# receiver.net
KiCad netlist of a schematic drawn in EAGLE
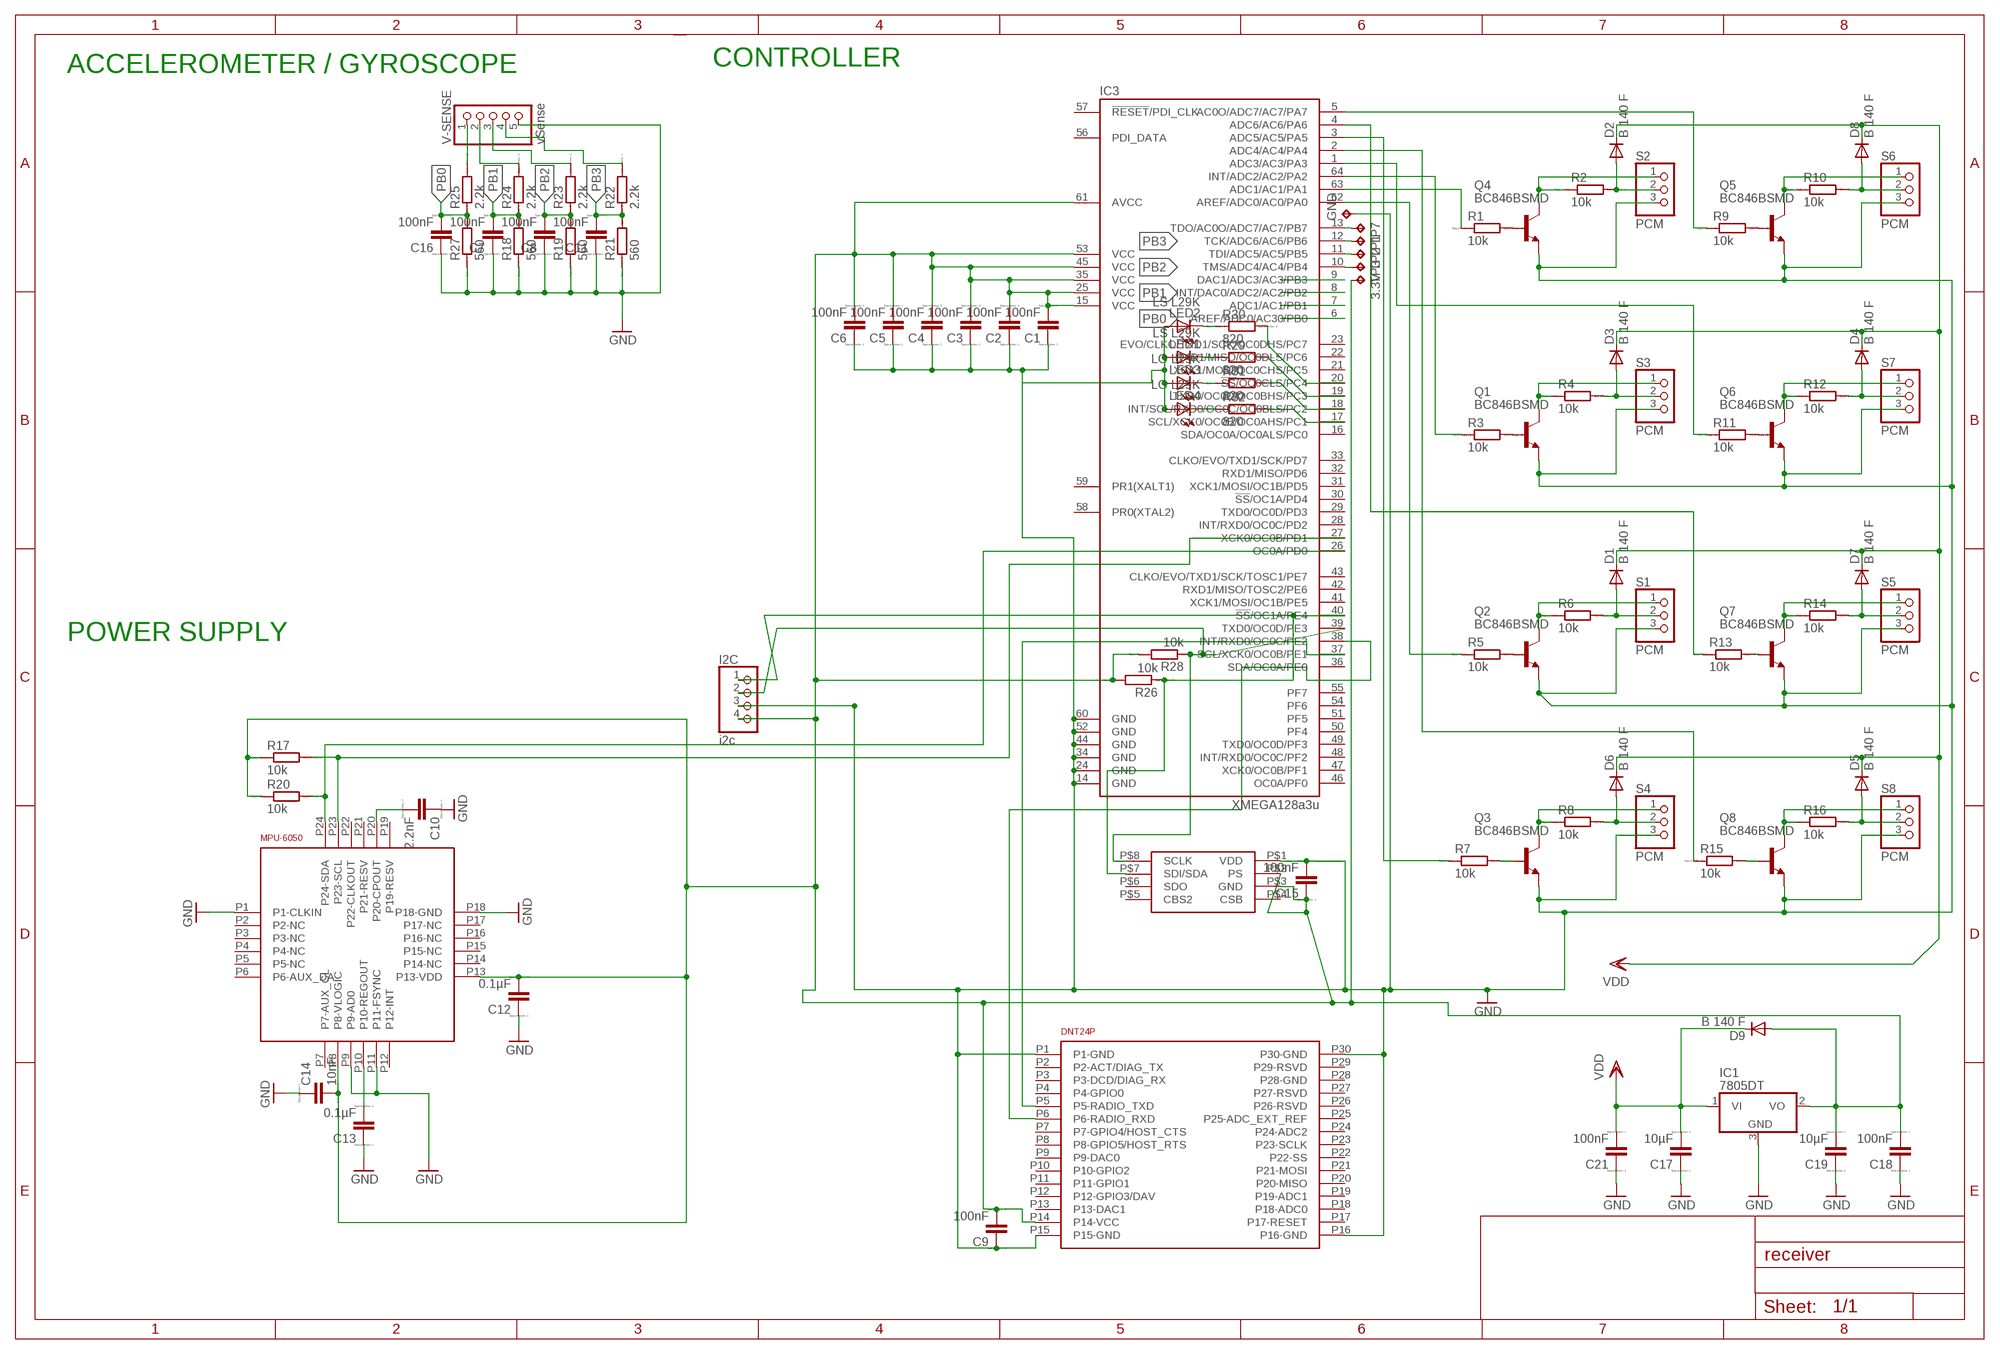
[diagram p0: schematic, sheet 1]

(export (version "E")
  (design (tool "Eeschema 10.0.6"))
  (components
    (comp (ref "3.3V")
      (value "TPTP08R")
      (footprint "eagle-import:TP08R")
      (libsource (lib "eagle-import") (part "TPTP08R"))
    )
    (comp (ref "C1")
      (value "100nF")
      (footprint "eagle-import:C0603")
      (libsource (lib "eagle-import") (part "CC0603"))
    )
    (comp (ref "C2")
      (value "100nF")
      (footprint "eagle-import:C0603")
      (libsource (lib "eagle-import") (part "CC0603"))
    )
    (comp (ref "C3")
      (value "100nF")
      (footprint "eagle-import:C0603")
      (libsource (lib "eagle-import") (part "CC0603"))
    )
    (comp (ref "C4")
      (value "100nF")
      (footprint "eagle-import:C0603")
      (libsource (lib "eagle-import") (part "CC0603"))
    )
    (comp (ref "C5")
      (value "100nF")
      (footprint "eagle-import:C0603")
      (libsource (lib "eagle-import") (part "CC0603"))
    )
    (comp (ref "C6")
      (value "100nF")
      (footprint "eagle-import:C0603")
      (libsource (lib "eagle-import") (part "CC0603"))
    )
    (comp (ref "C7")
      (value "100nF")
      (footprint "eagle-import:C0603")
      (libsource (lib "eagle-import") (part "CC0603"))
    )
    (comp (ref "C8")
      (value "100nF")
      (footprint "eagle-import:C0603")
      (libsource (lib "eagle-import") (part "CC0603"))
    )
    (comp (ref "C9")
      (value "100nF")
      (footprint "eagle-import:C0603")
      (libsource (lib "eagle-import") (part "CC0603"))
    )
    (comp (ref "C10")
      (value "2.2nF")
      (footprint "eagle-import:C0603")
      (libsource (lib "eagle-import") (part "CC0603"))
    )
    (comp (ref "C11")
      (value "100nF")
      (footprint "eagle-import:C0603")
      (libsource (lib "eagle-import") (part "CC0603"))
    )
    (comp (ref "C12")
      (value "0.1µF")
      (footprint "eagle-import:C0603")
      (libsource (lib "eagle-import") (part "CC0603"))
    )
    (comp (ref "C13")
      (value "0.1µF")
      (footprint "eagle-import:C0603")
      (libsource (lib "eagle-import") (part "CC0603"))
    )
    (comp (ref "C14")
      (value "10nF")
      (footprint "eagle-import:C0603")
      (libsource (lib "eagle-import") (part "CC0603"))
    )
    (comp (ref "C15")
      (value "100nF")
      (footprint "eagle-import:C0603")
      (libsource (lib "eagle-import") (part "CC0603"))
    )
    (comp (ref "C16")
      (value "100nF")
      (footprint "eagle-import:C0603")
      (libsource (lib "eagle-import") (part "CC0603"))
    )
    (comp (ref "C17")
      (value "10µF")
      (footprint "eagle-import:C0603")
      (libsource (lib "eagle-import") (part "CC0603"))
    )
    (comp (ref "C18")
      (value "100nF")
      (footprint "eagle-import:C0603")
      (libsource (lib "eagle-import") (part "CC0603"))
    )
    (comp (ref "C19")
      (value "10µF")
      (footprint "eagle-import:C0603")
      (libsource (lib "eagle-import") (part "CC0603"))
    )
    (comp (ref "C21")
      (value "100nF")
      (footprint "eagle-import:C0603")
      (libsource (lib "eagle-import") (part "CC0603"))
    )
    (comp (ref "D1")
      (value "B 140 F")
      (footprint "eagle-import:SOD-123_MINI-SMA")
      (libsource (lib "eagle-import") (part "CGRM400-G1"))
    )
    (comp (ref "D2")
      (value "B 140 F")
      (footprint "eagle-import:SOD-123_MINI-SMA")
      (libsource (lib "eagle-import") (part "CGRM400-G1"))
    )
    (comp (ref "D3")
      (value "B 140 F")
      (footprint "eagle-import:SOD-123_MINI-SMA")
      (libsource (lib "eagle-import") (part "CGRM400-G1"))
    )
    (comp (ref "D4")
      (value "B 140 F")
      (footprint "eagle-import:SOD-123_MINI-SMA")
      (libsource (lib "eagle-import") (part "CGRM400-G1"))
    )
    (comp (ref "D5")
      (value "B 140 F")
      (footprint "eagle-import:SOD-123_MINI-SMA")
      (libsource (lib "eagle-import") (part "CGRM400-G1"))
    )
    (comp (ref "D6")
      (value "B 140 F")
      (footprint "eagle-import:SOD-123_MINI-SMA")
      (libsource (lib "eagle-import") (part "CGRM400-G1"))
    )
    (comp (ref "D7")
      (value "B 140 F")
      (footprint "eagle-import:SOD-123_MINI-SMA")
      (libsource (lib "eagle-import") (part "CGRM400-G1"))
    )
    (comp (ref "D8")
      (value "B 140 F")
      (footprint "eagle-import:SOD-123_MINI-SMA")
      (libsource (lib "eagle-import") (part "CGRM400-G1"))
    )
    (comp (ref "D9")
      (value "B 140 F")
      (footprint "eagle-import:SOD-123_MINI-SMA")
      (libsource (lib "eagle-import") (part "CGRM400-G1"))
    )
    (comp (ref "GND")
      (value "TPTP08R")
      (footprint "eagle-import:TP08R")
      (libsource (lib "eagle-import") (part "TPTP08R"))
    )
    (comp (ref "I2C")
      (value "i2c")
      (footprint "eagle-import:1X04_90")
      (libsource (lib "eagle-import") (part "PINHD-1X4/90"))
    )
    (comp (ref "IC1")
      (value "7805DT")
      (footprint "eagle-import:TO252")
      (libsource (lib "eagle-import") (part "78DT05"))
    )
    (comp (ref "IC3")
      (value "XMEGA128a3u")
      (footprint "eagle-import:TQFP-64")
      (libsource (lib "eagle-import") (part "ATXMEGA##A3-64A"))
    )
    (comp (ref "LED1")
      (value "LS L29K")
      (footprint "eagle-import:CHIP-LED0603")
      (libsource (lib "eagle-import") (part "LEDCHIP-LED0603"))
    )
    (comp (ref "LED2")
      (value "LS L29K")
      (footprint "eagle-import:CHIP-LED0603")
      (libsource (lib "eagle-import") (part "LEDCHIP-LED0603"))
    )
    (comp (ref "LED3")
      (value "LO L29K")
      (footprint "eagle-import:CHIP-LED0603")
      (libsource (lib "eagle-import") (part "LEDCHIP-LED0603"))
    )
    (comp (ref "LED4")
      (value "LG L29K")
      (footprint "eagle-import:CHIP-LED0603")
      (libsource (lib "eagle-import") (part "LEDCHIP-LED0603"))
    )
    (comp (ref "Q1")
      (value "BC846BSMD")
      (footprint "eagle-import:SOT23")
      (libsource (lib "eagle-import") (part "BC846SMDB"))
    )
    (comp (ref "Q2")
      (value "BC846BSMD")
      (footprint "eagle-import:SOT23")
      (libsource (lib "eagle-import") (part "BC846SMDB"))
    )
    (comp (ref "Q3")
      (value "BC846BSMD")
      (footprint "eagle-import:SOT23")
      (libsource (lib "eagle-import") (part "BC846SMDB"))
    )
    (comp (ref "Q4")
      (value "BC846BSMD")
      (footprint "eagle-import:SOT23")
      (libsource (lib "eagle-import") (part "BC846SMDB"))
    )
    (comp (ref "Q5")
      (value "BC846BSMD")
      (footprint "eagle-import:SOT23")
      (libsource (lib "eagle-import") (part "BC846SMDB"))
    )
    (comp (ref "Q6")
      (value "BC846BSMD")
      (footprint "eagle-import:SOT23")
      (libsource (lib "eagle-import") (part "BC846SMDB"))
    )
    (comp (ref "Q7")
      (value "BC846BSMD")
      (footprint "eagle-import:SOT23")
      (libsource (lib "eagle-import") (part "BC846SMDB"))
    )
    (comp (ref "Q8")
      (value "BC846BSMD")
      (footprint "eagle-import:SOT23")
      (libsource (lib "eagle-import") (part "BC846SMDB"))
    )
    (comp (ref "R1")
      (value "10k")
      (footprint "eagle-import:R0603")
      (libsource (lib "eagle-import") (part "RR0603"))
    )
    (comp (ref "R2")
      (value "10k")
      (footprint "eagle-import:R0603")
      (libsource (lib "eagle-import") (part "RR0603"))
    )
    (comp (ref "R3")
      (value "10k")
      (footprint "eagle-import:R0603")
      (libsource (lib "eagle-import") (part "RR0603"))
    )
    (comp (ref "R4")
      (value "10k")
      (footprint "eagle-import:R0603")
      (libsource (lib "eagle-import") (part "RR0603"))
    )
    (comp (ref "R5")
      (value "10k")
      (footprint "eagle-import:R0603")
      (libsource (lib "eagle-import") (part "RR0603"))
    )
    (comp (ref "R6")
      (value "10k")
      (footprint "eagle-import:R0603")
      (libsource (lib "eagle-import") (part "RR0603"))
    )
    (comp (ref "R7")
      (value "10k")
      (footprint "eagle-import:R0603")
      (libsource (lib "eagle-import") (part "RR0603"))
    )
    (comp (ref "R8")
      (value "10k")
      (footprint "eagle-import:R0603")
      (libsource (lib "eagle-import") (part "RR0603"))
    )
    (comp (ref "R9")
      (value "10k")
      (footprint "eagle-import:R0603")
      (libsource (lib "eagle-import") (part "RR0603"))
    )
    (comp (ref "R10")
      (value "10k")
      (footprint "eagle-import:R0603")
      (libsource (lib "eagle-import") (part "RR0603"))
    )
    (comp (ref "R11")
      (value "10k")
      (footprint "eagle-import:R0603")
      (libsource (lib "eagle-import") (part "RR0603"))
    )
    (comp (ref "R12")
      (value "10k")
      (footprint "eagle-import:R0603")
      (libsource (lib "eagle-import") (part "RR0603"))
    )
    (comp (ref "R13")
      (value "10k")
      (footprint "eagle-import:R0603")
      (libsource (lib "eagle-import") (part "RR0603"))
    )
    (comp (ref "R14")
      (value "10k")
      (footprint "eagle-import:R0603")
      (libsource (lib "eagle-import") (part "RR0603"))
    )
    (comp (ref "R15")
      (value "10k")
      (footprint "eagle-import:R0603")
      (libsource (lib "eagle-import") (part "RR0603"))
    )
    (comp (ref "R16")
      (value "10k")
      (footprint "eagle-import:R0603")
      (libsource (lib "eagle-import") (part "RR0603"))
    )
    (comp (ref "R17")
      (value "10k")
      (footprint "eagle-import:R0603")
      (libsource (lib "eagle-import") (part "RR0603"))
    )
    (comp (ref "R18")
      (value "560")
      (footprint "eagle-import:R0603")
      (libsource (lib "eagle-import") (part "RR0603"))
    )
    (comp (ref "R19")
      (value "560")
      (footprint "eagle-import:R0603")
      (libsource (lib "eagle-import") (part "RR0603"))
    )
    (comp (ref "R20")
      (value "10k")
      (footprint "eagle-import:R0603")
      (libsource (lib "eagle-import") (part "RR0603"))
    )
    (comp (ref "R21")
      (value "560")
      (footprint "eagle-import:R0603")
      (libsource (lib "eagle-import") (part "RR0603"))
    )
    (comp (ref "R22")
      (value "2.2k")
      (footprint "eagle-import:R0603")
      (libsource (lib "eagle-import") (part "RR0603"))
    )
    (comp (ref "R23")
      (value "2.2k")
      (footprint "eagle-import:R0603")
      (libsource (lib "eagle-import") (part "RR0603"))
    )
    (comp (ref "R24")
      (value "2.2k")
      (footprint "eagle-import:R0603")
      (libsource (lib "eagle-import") (part "RR0603"))
    )
    (comp (ref "R25")
      (value "2.2k")
      (footprint "eagle-import:R0603")
      (libsource (lib "eagle-import") (part "RR0603"))
    )
    (comp (ref "R26")
      (value "10k")
      (footprint "eagle-import:R0603")
      (libsource (lib "eagle-import") (part "RR0603"))
    )
    (comp (ref "R27")
      (value "560")
      (footprint "eagle-import:R0603")
      (libsource (lib "eagle-import") (part "RR0603"))
    )
    (comp (ref "R28")
      (value "10k")
      (footprint "eagle-import:R0603")
      (libsource (lib "eagle-import") (part "RR0603"))
    )
    (comp (ref "R29")
      (value "820")
      (footprint "eagle-import:R0603")
      (libsource (lib "eagle-import") (part "RR0603"))
    )
    (comp (ref "R30")
      (value "820")
      (footprint "eagle-import:R0603")
      (libsource (lib "eagle-import") (part "RR0603"))
    )
    (comp (ref "R31")
      (value "820")
      (footprint "eagle-import:R0603")
      (libsource (lib "eagle-import") (part "RR0603"))
    )
    (comp (ref "R32")
      (value "820")
      (footprint "eagle-import:R0603")
      (libsource (lib "eagle-import") (part "RR0603"))
    )
    (comp (ref "S1")
      (value "PCM")
      (footprint "eagle-import:1X03")
      (libsource (lib "eagle-import") (part "PINHD-1X3"))
    )
    (comp (ref "S2")
      (value "PCM")
      (footprint "eagle-import:1X03")
      (libsource (lib "eagle-import") (part "PINHD-1X3"))
    )
    (comp (ref "S3")
      (value "PCM")
      (footprint "eagle-import:1X03")
      (libsource (lib "eagle-import") (part "PINHD-1X3"))
    )
    (comp (ref "S4")
      (value "PCM")
      (footprint "eagle-import:1X03")
      (libsource (lib "eagle-import") (part "PINHD-1X3"))
    )
    (comp (ref "S5")
      (value "PCM")
      (footprint "eagle-import:1X03")
      (libsource (lib "eagle-import") (part "PINHD-1X3"))
    )
    (comp (ref "S6")
      (value "PCM")
      (footprint "eagle-import:1X03")
      (libsource (lib "eagle-import") (part "PINHD-1X3"))
    )
    (comp (ref "S7")
      (value "PCM")
      (footprint "eagle-import:1X03")
      (libsource (lib "eagle-import") (part "PINHD-1X3"))
    )
    (comp (ref "S8")
      (value "PCM")
      (footprint "eagle-import:1X03")
      (libsource (lib "eagle-import") (part "PINHD-1X3"))
    )
    (comp (ref "TP1")
      (value "TPTP08R")
      (footprint "eagle-import:TP08R")
      (libsource (lib "eagle-import") (part "TPTP08R"))
    )
    (comp (ref "TP2")
      (value "TPTP08R")
      (footprint "eagle-import:TP08R")
      (libsource (lib "eagle-import") (part "TPTP08R"))
    )
    (comp (ref "TP3")
      (value "TPTP08R")
      (footprint "eagle-import:TP08R")
      (libsource (lib "eagle-import") (part "TPTP08R"))
    )
    (comp (ref "TP7")
      (value "TPTP08R")
      (footprint "eagle-import:TP08R")
      (libsource (lib "eagle-import") (part "TPTP08R"))
    )
    (comp (ref "U$1")
      (value "DNT24P_RADIO_MODULE")
      (footprint "eagle-import:DNT24P_RADIO_MODULE")
      (libsource (lib "eagle-import") (part "DNT24P_RADIO_MODULE"))
    )
    (comp (ref "U$2")
      (value "MS5611")
      (footprint "eagle-import:01BA03")
      (libsource (lib "eagle-import") (part "MS5611"))
    )
    (comp (ref "U$3")
      (value "MPU-6050_ACC_GYRO")
      (footprint "eagle-import:MPU-6050_ACC_GYRO")
      (libsource (lib "eagle-import") (part "MPU-6050_ACC_GYRO"))
    )
    (comp (ref "V-SENSE")
      (value "vSense")
      (footprint "eagle-import:1X05_90")
      (libsource (lib "eagle-import") (part "PINHD-1X5/90"))
    )
  )
  (nets
    (net (code "1") (name "GND") (class "Default")
      (node (ref "C1") (pin "1") (pinfunction "1_1") (pintype "passive"))
      (node (ref "C10") (pin "1") (pinfunction "1_1") (pintype "passive"))
      (node (ref "C11") (pin "1") (pinfunction "1_1") (pintype "passive"))
      (node (ref "C12") (pin "1") (pinfunction "1_1") (pintype "passive"))
      (node (ref "C13") (pin "1") (pinfunction "1_1") (pintype "passive"))
      (node (ref "C14") (pin "1") (pinfunction "1_1") (pintype "passive"))
      (node (ref "C15") (pin "2") (pinfunction "2_2") (pintype "passive"))
      (node (ref "C16") (pin "1") (pinfunction "1_1") (pintype "passive"))
      (node (ref "C17") (pin "1") (pinfunction "1_1") (pintype "passive"))
      (node (ref "C18") (pin "1") (pinfunction "1_1") (pintype "passive"))
      (node (ref "C19") (pin "1") (pinfunction "1_1") (pintype "passive"))
      (node (ref "C2") (pin "1") (pinfunction "1_1") (pintype "passive"))
      (node (ref "C21") (pin "1") (pinfunction "1_1") (pintype "passive"))
      (node (ref "C3") (pin "1") (pinfunction "1_1") (pintype "passive"))
      (node (ref "C4") (pin "1") (pinfunction "1_1") (pintype "passive"))
      (node (ref "C5") (pin "1") (pinfunction "1_1") (pintype "passive"))
      (node (ref "C6") (pin "1") (pinfunction "1_1") (pintype "passive"))
      (node (ref "C7") (pin "1") (pinfunction "1_1") (pintype "passive"))
      (node (ref "C8") (pin "1") (pinfunction "1_1") (pintype "passive"))
      (node (ref "C9") (pin "1") (pinfunction "1_1") (pintype "passive"))
      (node (ref "GND") (pin "TP") (pinfunction "TP_TP") (pintype "input"))
      (node (ref "I2C") (pin "3") (pinfunction "3_3") (pintype "passive"))
      (node (ref "IC1") (pin "3") (pinfunction "GND_3") (pintype "passive"))
      (node (ref "IC3") (pin "14") (pinfunction "GND_14") (pintype "power_in"))
      (node (ref "IC3") (pin "24") (pinfunction "GND_24") (pintype "power_in"))
      (node (ref "IC3") (pin "34") (pinfunction "GND_34") (pintype "power_in"))
      (node (ref "IC3") (pin "44") (pinfunction "GND_44") (pintype "power_in"))
      (node (ref "IC3") (pin "52") (pinfunction "GND_52") (pintype "power_in"))
      (node (ref "IC3") (pin "60") (pinfunction "GND_60") (pintype "power_in"))
      (node (ref "LED1") (pin "A") (pinfunction "A_A") (pintype "passive"))
      (node (ref "LED2") (pin "A") (pinfunction "A_A") (pintype "passive"))
      (node (ref "LED3") (pin "A") (pinfunction "A_A") (pintype "passive"))
      (node (ref "LED4") (pin "A") (pinfunction "A_A") (pintype "passive"))
      (node (ref "Q1") (pin "2") (pinfunction "E_2") (pintype "passive"))
      (node (ref "Q2") (pin "2") (pinfunction "E_2") (pintype "passive"))
      (node (ref "Q3") (pin "2") (pinfunction "E_2") (pintype "passive"))
      (node (ref "Q4") (pin "2") (pinfunction "E_2") (pintype "passive"))
      (node (ref "Q5") (pin "2") (pinfunction "E_2") (pintype "passive"))
      (node (ref "Q6") (pin "2") (pinfunction "E_2") (pintype "passive"))
      (node (ref "Q7") (pin "2") (pinfunction "E_2") (pintype "passive"))
      (node (ref "Q8") (pin "2") (pinfunction "E_2") (pintype "passive"))
      (node (ref "R18") (pin "1") (pinfunction "1_1") (pintype "passive"))
      (node (ref "R19") (pin "1") (pinfunction "1_1") (pintype "passive"))
      (node (ref "R21") (pin "1") (pinfunction "1_1") (pintype "passive"))
      (node (ref "R27") (pin "1") (pinfunction "1_1") (pintype "passive"))
      (node (ref "S1") (pin "3") (pinfunction "3_3") (pintype "passive"))
      (node (ref "S2") (pin "3") (pinfunction "3_3") (pintype "passive"))
      (node (ref "S3") (pin "3") (pinfunction "3_3") (pintype "passive"))
      (node (ref "S4") (pin "3") (pinfunction "3_3") (pintype "passive"))
      (node (ref "S5") (pin "3") (pinfunction "3_3") (pintype "passive"))
      (node (ref "S6") (pin "3") (pinfunction "3_3") (pintype "passive"))
      (node (ref "S7") (pin "3") (pinfunction "3_3") (pintype "passive"))
      (node (ref "S8") (pin "3") (pinfunction "3_3") (pintype "passive"))
      (node (ref "U$1") (pin "P1") (pinfunction "P1-GND_P1") (pintype "bidirectional"))
      (node (ref "U$1") (pin "P15") (pinfunction "P15-GND_P15") (pintype "bidirectional"))
      (node (ref "U$1") (pin "P16") (pinfunction "P16-GND_P16") (pintype "bidirectional"))
      (node (ref "U$1") (pin "P30") (pinfunction "P30-GND_P30") (pintype "bidirectional"))
      (node (ref "U$2") (pin "P$1") (pinfunction "VDD_P$1") (pintype "bidirectional"))
      (node (ref "U$3") (pin "P1") (pinfunction "P1-CLKIN_P1") (pintype "bidirectional"))
      (node (ref "U$3") (pin "P11") (pinfunction "P11-FSYNC_P11") (pintype "bidirectional"))
      (node (ref "U$3") (pin "P18") (pinfunction "P18-GND_P18") (pintype "bidirectional"))
      (node (ref "U$3") (pin "P9") (pinfunction "P9-AD0_P9") (pintype "bidirectional"))
      (node (ref "V-SENSE") (pin "5") (pinfunction "5_5") (pintype "passive"))
    )
    (net (code "2") (name "Net-(D1-PadA)") (class "Default")
      (node (ref "D1") (pin "A") (pinfunction "A_A") (pintype "passive"))
      (node (ref "R6") (pin "2") (pinfunction "2_2") (pintype "passive"))
      (node (ref "S1") (pin "2") (pinfunction "2_2") (pintype "passive"))
    )
    (net (code "3") (name "Net-(D2-PadA)") (class "Default")
      (node (ref "D2") (pin "A") (pinfunction "A_A") (pintype "passive"))
      (node (ref "R2") (pin "2") (pinfunction "2_2") (pintype "passive"))
      (node (ref "S2") (pin "2") (pinfunction "2_2") (pintype "passive"))
    )
    (net (code "4") (name "Net-(D3-PadA)") (class "Default")
      (node (ref "D3") (pin "A") (pinfunction "A_A") (pintype "passive"))
      (node (ref "R4") (pin "2") (pinfunction "2_2") (pintype "passive"))
      (node (ref "S3") (pin "2") (pinfunction "2_2") (pintype "passive"))
    )
    (net (code "5") (name "Net-(D4-PadA)") (class "Default")
      (node (ref "D4") (pin "A") (pinfunction "A_A") (pintype "passive"))
      (node (ref "R12") (pin "2") (pinfunction "2_2") (pintype "passive"))
      (node (ref "S7") (pin "2") (pinfunction "2_2") (pintype "passive"))
    )
    (net (code "6") (name "Net-(D5-PadA)") (class "Default")
      (node (ref "D5") (pin "A") (pinfunction "A_A") (pintype "passive"))
      (node (ref "R16") (pin "2") (pinfunction "2_2") (pintype "passive"))
      (node (ref "S8") (pin "2") (pinfunction "2_2") (pintype "passive"))
    )
    (net (code "7") (name "Net-(D6-PadA)") (class "Default")
      (node (ref "D6") (pin "A") (pinfunction "A_A") (pintype "passive"))
      (node (ref "R8") (pin "2") (pinfunction "2_2") (pintype "passive"))
      (node (ref "S4") (pin "2") (pinfunction "2_2") (pintype "passive"))
    )
    (net (code "8") (name "Net-(D7-PadA)") (class "Default")
      (node (ref "D7") (pin "A") (pinfunction "A_A") (pintype "passive"))
      (node (ref "R14") (pin "2") (pinfunction "2_2") (pintype "passive"))
      (node (ref "S5") (pin "2") (pinfunction "2_2") (pintype "passive"))
    )
    (net (code "9") (name "Net-(D8-PadA)") (class "Default")
      (node (ref "D8") (pin "A") (pinfunction "A_A") (pintype "passive"))
      (node (ref "R10") (pin "2") (pinfunction "2_2") (pintype "passive"))
      (node (ref "S6") (pin "2") (pinfunction "2_2") (pintype "passive"))
    )
    (net (code "10") (name "Net-(IC1-VO)") (class "Default")
      (node (ref "3.3V") (pin "TP") (pinfunction "TP_TP") (pintype "input"))
      (node (ref "C1") (pin "2") (pinfunction "2_2") (pintype "passive"))
      (node (ref "C12") (pin "2") (pinfunction "2_2") (pintype "passive"))
      (node (ref "C14") (pin "2") (pinfunction "2_2") (pintype "passive"))
      (node (ref "C15") (pin "1") (pinfunction "1_1") (pintype "passive"))
      (node (ref "C18") (pin "2") (pinfunction "2_2") (pintype "passive"))
      (node (ref "C19") (pin "2") (pinfunction "2_2") (pintype "passive"))
      (node (ref "C2") (pin "2") (pinfunction "2_2") (pintype "passive"))
      (node (ref "C3") (pin "2") (pinfunction "2_2") (pintype "passive"))
      (node (ref "C4") (pin "2") (pinfunction "2_2") (pintype "passive"))
      (node (ref "C5") (pin "2") (pinfunction "2_2") (pintype "passive"))
      (node (ref "C6") (pin "2") (pinfunction "2_2") (pintype "passive"))
      (node (ref "C9") (pin "2") (pinfunction "2_2") (pintype "passive"))
      (node (ref "D9") (pin "A") (pinfunction "A_A") (pintype "passive"))
      (node (ref "I2C") (pin "4") (pinfunction "4_4") (pintype "passive"))
      (node (ref "IC1") (pin "2") (pinfunction "VO_2") (pintype "passive"))
      (node (ref "IC3") (pin "15") (pinfunction "VCC_15") (pintype "power_in"))
      (node (ref "IC3") (pin "25") (pinfunction "VCC_25") (pintype "power_in"))
      (node (ref "IC3") (pin "35") (pinfunction "VCC_35") (pintype "power_in"))
      (node (ref "IC3") (pin "45") (pinfunction "VCC_45") (pintype "power_in"))
      (node (ref "IC3") (pin "53") (pinfunction "VCC_53") (pintype "power_in"))
      (node (ref "IC3") (pin "61") (pinfunction "AVCC_61") (pintype "power_in"))
      (node (ref "R17") (pin "1") (pinfunction "1_1") (pintype "passive"))
      (node (ref "R20") (pin "1") (pinfunction "1_1") (pintype "passive"))
      (node (ref "R26") (pin "2") (pinfunction "2_2") (pintype "passive"))
      (node (ref "R28") (pin "2") (pinfunction "2_2") (pintype "passive"))
      (node (ref "U$1") (pin "P14") (pinfunction "P14-VCC_P14") (pintype "bidirectional"))
      (node (ref "U$2") (pin "P$2") (pinfunction "PS_P$2") (pintype "bidirectional"))
      (node (ref "U$2") (pin "P$3") (pinfunction "GND_P$3") (pintype "bidirectional"))
      (node (ref "U$3") (pin "P13") (pinfunction "P13-VDD_P13") (pintype "bidirectional"))
      (node (ref "U$3") (pin "P8") (pinfunction "P8-VLOGIC_P8") (pintype "bidirectional"))
    )
    (net (code "11") (name "Net-(IC3-AC0O{slash}ADC7{slash}AC7{slash}PA7)") (class "Default")
      (node (ref "IC3") (pin "5") (pinfunction "AC0O/ADC7/AC7/PA7_5") (pintype "bidirectional"))
      (node (ref "R9") (pin "1") (pinfunction "1_1") (pintype "passive"))
    )
    (net (code "12") (name "Net-(IC3-ADC1{slash}AC1{slash}PA1)") (class "Default")
      (node (ref "IC3") (pin "63") (pinfunction "ADC1/AC1/PA1_63") (pintype "bidirectional"))
      (node (ref "R1") (pin "1") (pinfunction "1_1") (pintype "passive"))
    )
    (net (code "13") (name "Net-(IC3-ADC3{slash}AC3{slash}PA3)") (class "Default")
      (node (ref "IC3") (pin "1") (pinfunction "ADC3/AC3/PA3_1") (pintype "bidirectional"))
      (node (ref "R11") (pin "1") (pinfunction "1_1") (pintype "passive"))
    )
    (net (code "14") (name "Net-(IC3-ADC4{slash}AC4{slash}PA4)") (class "Default")
      (node (ref "IC3") (pin "2") (pinfunction "ADC4/AC4/PA4_2") (pintype "bidirectional"))
      (node (ref "R15") (pin "1") (pinfunction "1_1") (pintype "passive"))
    )
    (net (code "15") (name "Net-(IC3-ADC5{slash}AC5{slash}PA5)") (class "Default")
      (node (ref "IC3") (pin "3") (pinfunction "ADC5/AC5/PA5_3") (pintype "bidirectional"))
      (node (ref "R7") (pin "1") (pinfunction "1_1") (pintype "passive"))
    )
    (net (code "16") (name "Net-(IC3-ADC6{slash}AC6{slash}PA6)") (class "Default")
      (node (ref "IC3") (pin "4") (pinfunction "ADC6/AC6/PA6_4") (pintype "bidirectional"))
      (node (ref "R13") (pin "1") (pinfunction "1_1") (pintype "passive"))
    )
    (net (code "17") (name "Net-(IC3-AREF{slash}ADC0{slash}AC0{slash}PA0)") (class "Default")
      (node (ref "IC3") (pin "62") (pinfunction "AREF/ADC0/AC0/PA0_62") (pintype "bidirectional"))
      (node (ref "R5") (pin "1") (pinfunction "1_1") (pintype "passive"))
    )
    (net (code "18") (name "Net-(IC3-INT{slash}ADC2{slash}AC2{slash}PA2)") (class "Default")
      (node (ref "IC3") (pin "64") (pinfunction "INT/ADC2/AC2/PA2_64") (pintype "bidirectional"))
      (node (ref "R3") (pin "1") (pinfunction "1_1") (pintype "passive"))
    )
    (net (code "19") (name "Net-(IC3-INT{slash}RXD0{slash}OC0C{slash}PE2)") (class "Default")
      (node (ref "IC3") (pin "38") (pinfunction "INT/RXD0/OC0C/PE2_38") (pintype "bidirectional"))
      (node (ref "U$1") (pin "P6") (pinfunction "P6-RADIO_RXD_P6") (pintype "bidirectional"))
    )
    (net (code "20") (name "Net-(IC3-INT{slash}SCL{slash}RXD0{slash}OC0C{slash}OC0BLS{slash}PC2)") (class "Default")
      (node (ref "IC3") (pin "18") (pinfunction "INT/SCL/RXD0/OC0C/OC0BLS/PC2_18") (pintype "bidirectional"))
      (node (ref "R31") (pin "2") (pinfunction "2_2") (pintype "passive"))
    )
    (net (code "21") (name "Net-(IC3-OC0A{slash}PD0)") (class "Default")
      (node (ref "IC3") (pin "26") (pinfunction "OC0A/PD0_26") (pintype "bidirectional"))
      (node (ref "R20") (pin "2") (pinfunction "2_2") (pintype "passive"))
      (node (ref "U$3") (pin "P24") (pinfunction "P24-SDA_P24") (pintype "bidirectional"))
    )
    (net (code "22") (name "Net-(IC3-SCL{slash}XCK0{slash}OC0B{slash}OC0AHS{slash}PC1)") (class "Default")
      (node (ref "IC3") (pin "17") (pinfunction "SCL/XCK0/OC0B/OC0AHS/PC1_17") (pintype "bidirectional"))
      (node (ref "R32") (pin "2") (pinfunction "2_2") (pintype "passive"))
    )
    (net (code "23") (name "Net-(IC3-SCL{slash}XCK0{slash}OC0B{slash}PE1)") (class "Default")
      (node (ref "IC3") (pin "37") (pinfunction "SCL/XCK0/OC0B/PE1_37") (pintype "bidirectional"))
      (node (ref "U$1") (pin "P5") (pinfunction "P5-RADIO_TXD_P5") (pintype "bidirectional"))
    )
    (net (code "24") (name "Net-(IC3-TCK{slash}ADC6{slash}AC6{slash}PB6)") (class "Default")
      (node (ref "IC3") (pin "12") (pinfunction "TCK/ADC6/AC6/PB6_12") (pintype "bidirectional"))
      (node (ref "TP1") (pin "TP") (pinfunction "TP_TP") (pintype "input"))
    )
    (net (code "25") (name "Net-(IC3-TDI{slash}ADC5{slash}AC5{slash}PB5)") (class "Default")
      (node (ref "IC3") (pin "11") (pinfunction "TDI/ADC5/AC5/PB5_11") (pintype "bidirectional"))
      (node (ref "TP2") (pin "TP") (pinfunction "TP_TP") (pintype "input"))
    )
    (net (code "26") (name "Net-(IC3-TDO{slash}AC0O{slash}ADC7{slash}AC7{slash}PB7)") (class "Default")
      (node (ref "IC3") (pin "13") (pinfunction "TDO/AC0O/ADC7/AC7/PB7_13") (pintype "bidirectional"))
      (node (ref "TP7") (pin "TP") (pinfunction "TP_TP") (pintype "input"))
    )
    (net (code "27") (name "Net-(IC3-TMS{slash}ADC4{slash}AC4{slash}PB4)") (class "Default")
      (node (ref "IC3") (pin "10") (pinfunction "TMS/ADC4/AC4/PB4_10") (pintype "bidirectional"))
      (node (ref "TP3") (pin "TP") (pinfunction "TP_TP") (pintype "input"))
    )
    (net (code "28") (name "Net-(IC3-TXD0{slash}OC0D{slash}OC0BHS{slash}PC3)") (class "Default")
      (node (ref "IC3") (pin "19") (pinfunction "TXD0/OC0D/OC0BHS/PC3_19") (pintype "bidirectional"))
      (node (ref "R29") (pin "2") (pinfunction "2_2") (pintype "passive"))
    )
    (net (code "29") (name "Net-(IC3-TXD0{slash}OC0D{slash}PE3)") (class "Default")
      (node (ref "I2C") (pin "2") (pinfunction "2_2") (pintype "passive"))
      (node (ref "IC3") (pin "39") (pinfunction "TXD0/OC0D/PE3_39") (pintype "bidirectional"))
      (node (ref "R28") (pin "1") (pinfunction "1_1") (pintype "passive"))
      (node (ref "U$2") (pin "P$8") (pinfunction "SCLK_P$8") (pintype "bidirectional"))
    )
    (net (code "30") (name "Net-(IC3-XCK0{slash}OC0B{slash}PD1)") (class "Default")
      (node (ref "IC3") (pin "27") (pinfunction "XCK0/OC0B/PD1_27") (pintype "bidirectional"))
      (node (ref "R17") (pin "2") (pinfunction "2_2") (pintype "passive"))
      (node (ref "U$3") (pin "P23") (pinfunction "P23-SCL_P23") (pintype "bidirectional"))
    )
    (net (code "31") (name "Net-(IC3-~{SS}{slash}OC0CLS{slash}PC4)") (class "Default")
      (node (ref "IC3") (pin "20") (pinfunction "~{SS}/OC0CLS/PC4_20") (pintype "bidirectional"))
      (node (ref "R30") (pin "2") (pinfunction "2_2") (pintype "passive"))
    )
    (net (code "32") (name "Net-(IC3-~{SS}{slash}OC1A{slash}PE4)") (class "Default")
      (node (ref "I2C") (pin "1") (pinfunction "1_1") (pintype "passive"))
      (node (ref "IC3") (pin "40") (pinfunction "~{SS}/OC1A/PE4_40") (pintype "bidirectional"))
      (node (ref "R26") (pin "1") (pinfunction "1_1") (pintype "passive"))
      (node (ref "U$2") (pin "P$7") (pinfunction "SDI/SDA_P$7") (pintype "bidirectional"))
    )
    (net (code "33") (name "Net-(LED1-PadC)") (class "Default")
      (node (ref "LED1") (pin "C") (pinfunction "C_C") (pintype "passive"))
      (node (ref "R29") (pin "1") (pinfunction "1_1") (pintype "passive"))
    )
    (net (code "34") (name "Net-(LED2-PadC)") (class "Default")
      (node (ref "LED2") (pin "C") (pinfunction "C_C") (pintype "passive"))
      (node (ref "R30") (pin "1") (pinfunction "1_1") (pintype "passive"))
    )
    (net (code "35") (name "Net-(LED3-PadC)") (class "Default")
      (node (ref "LED3") (pin "C") (pinfunction "C_C") (pintype "passive"))
      (node (ref "R31") (pin "1") (pinfunction "1_1") (pintype "passive"))
    )
    (net (code "36") (name "Net-(LED4-PadC)") (class "Default")
      (node (ref "LED4") (pin "C") (pinfunction "C_C") (pintype "passive"))
      (node (ref "R32") (pin "1") (pinfunction "1_1") (pintype "passive"))
    )
    (net (code "37") (name "Net-(Q1-B)") (class "Default")
      (node (ref "Q1") (pin "1") (pinfunction "B_1") (pintype "passive"))
      (node (ref "R3") (pin "2") (pinfunction "2_2") (pintype "passive"))
    )
    (net (code "38") (name "Net-(Q1-C)") (class "Default")
      (node (ref "Q1") (pin "3") (pinfunction "C_3") (pintype "passive"))
      (node (ref "R4") (pin "1") (pinfunction "1_1") (pintype "passive"))
      (node (ref "S3") (pin "1") (pinfunction "1_1") (pintype "passive"))
    )
    (net (code "39") (name "Net-(Q2-B)") (class "Default")
      (node (ref "Q2") (pin "1") (pinfunction "B_1") (pintype "passive"))
      (node (ref "R5") (pin "2") (pinfunction "2_2") (pintype "passive"))
    )
    (net (code "40") (name "Net-(Q2-C)") (class "Default")
      (node (ref "Q2") (pin "3") (pinfunction "C_3") (pintype "passive"))
      (node (ref "R6") (pin "1") (pinfunction "1_1") (pintype "passive"))
      (node (ref "S1") (pin "1") (pinfunction "1_1") (pintype "passive"))
    )
    (net (code "41") (name "Net-(Q3-B)") (class "Default")
      (node (ref "Q3") (pin "1") (pinfunction "B_1") (pintype "passive"))
      (node (ref "R7") (pin "2") (pinfunction "2_2") (pintype "passive"))
    )
    (net (code "42") (name "Net-(Q3-C)") (class "Default")
      (node (ref "Q3") (pin "3") (pinfunction "C_3") (pintype "passive"))
      (node (ref "R8") (pin "1") (pinfunction "1_1") (pintype "passive"))
      (node (ref "S4") (pin "1") (pinfunction "1_1") (pintype "passive"))
    )
    (net (code "43") (name "Net-(Q4-B)") (class "Default")
      (node (ref "Q4") (pin "1") (pinfunction "B_1") (pintype "passive"))
      (node (ref "R1") (pin "2") (pinfunction "2_2") (pintype "passive"))
    )
    (net (code "44") (name "Net-(Q4-C)") (class "Default")
      (node (ref "Q4") (pin "3") (pinfunction "C_3") (pintype "passive"))
      (node (ref "R2") (pin "1") (pinfunction "1_1") (pintype "passive"))
      (node (ref "S2") (pin "1") (pinfunction "1_1") (pintype "passive"))
    )
    (net (code "45") (name "Net-(Q5-B)") (class "Default")
      (node (ref "Q5") (pin "1") (pinfunction "B_1") (pintype "passive"))
      (node (ref "R9") (pin "2") (pinfunction "2_2") (pintype "passive"))
    )
    (net (code "46") (name "Net-(Q5-C)") (class "Default")
      (node (ref "Q5") (pin "3") (pinfunction "C_3") (pintype "passive"))
      (node (ref "R10") (pin "1") (pinfunction "1_1") (pintype "passive"))
      (node (ref "S6") (pin "1") (pinfunction "1_1") (pintype "passive"))
    )
    (net (code "47") (name "Net-(Q6-B)") (class "Default")
      (node (ref "Q6") (pin "1") (pinfunction "B_1") (pintype "passive"))
      (node (ref "R11") (pin "2") (pinfunction "2_2") (pintype "passive"))
    )
    (net (code "48") (name "Net-(Q6-C)") (class "Default")
      (node (ref "Q6") (pin "3") (pinfunction "C_3") (pintype "passive"))
      (node (ref "R12") (pin "1") (pinfunction "1_1") (pintype "passive"))
      (node (ref "S7") (pin "1") (pinfunction "1_1") (pintype "passive"))
    )
    (net (code "49") (name "Net-(Q7-B)") (class "Default")
      (node (ref "Q7") (pin "1") (pinfunction "B_1") (pintype "passive"))
      (node (ref "R13") (pin "2") (pinfunction "2_2") (pintype "passive"))
    )
    (net (code "50") (name "Net-(Q7-C)") (class "Default")
      (node (ref "Q7") (pin "3") (pinfunction "C_3") (pintype "passive"))
      (node (ref "R14") (pin "1") (pinfunction "1_1") (pintype "passive"))
      (node (ref "S5") (pin "1") (pinfunction "1_1") (pintype "passive"))
    )
    (net (code "51") (name "Net-(Q8-B)") (class "Default")
      (node (ref "Q8") (pin "1") (pinfunction "B_1") (pintype "passive"))
      (node (ref "R15") (pin "2") (pinfunction "2_2") (pintype "passive"))
    )
    (net (code "52") (name "Net-(Q8-C)") (class "Default")
      (node (ref "Q8") (pin "3") (pinfunction "C_3") (pintype "passive"))
      (node (ref "R16") (pin "1") (pinfunction "1_1") (pintype "passive"))
      (node (ref "S8") (pin "1") (pinfunction "1_1") (pintype "passive"))
    )
    (net (code "53") (name "Net-(R22-Pad2)") (class "Default")
      (node (ref "R22") (pin "2") (pinfunction "2_2") (pintype "passive"))
      (node (ref "V-SENSE") (pin "4") (pinfunction "4_4") (pintype "passive"))
    )
    (net (code "54") (name "Net-(R23-Pad2)") (class "Default")
      (node (ref "R23") (pin "2") (pinfunction "2_2") (pintype "passive"))
      (node (ref "V-SENSE") (pin "3") (pinfunction "3_3") (pintype "passive"))
    )
    (net (code "55") (name "Net-(R24-Pad2)") (class "Default")
      (node (ref "R24") (pin "2") (pinfunction "2_2") (pintype "passive"))
      (node (ref "V-SENSE") (pin "2") (pinfunction "2_2") (pintype "passive"))
    )
    (net (code "56") (name "Net-(R25-Pad2)") (class "Default")
      (node (ref "R25") (pin "2") (pinfunction "2_2") (pintype "passive"))
      (node (ref "V-SENSE") (pin "1") (pinfunction "1_1") (pintype "passive"))
    )
    (net (code "57") (name "Net-(U$3-P10-REGOUT)") (class "Default")
      (node (ref "C13") (pin "2") (pinfunction "2_2") (pintype "passive"))
      (node (ref "U$3") (pin "P10") (pinfunction "P10-REGOUT_P10") (pintype "bidirectional"))
    )
    (net (code "58") (name "Net-(U$3-P20-CPOUT)") (class "Default")
      (node (ref "C10") (pin "2") (pinfunction "2_2") (pintype "passive"))
      (node (ref "U$3") (pin "P20") (pinfunction "P20-CPOUT_P20") (pintype "bidirectional"))
    )
    (net (code "59") (name "PB0") (class "Default")
      (node (ref "C16") (pin "2") (pinfunction "2_2") (pintype "passive"))
      (node (ref "IC3") (pin "6") (pinfunction "AREF/ADC0/AC30/PB0_6") (pintype "bidirectional"))
      (node (ref "R25") (pin "1") (pinfunction "1_1") (pintype "passive"))
      (node (ref "R27") (pin "2") (pinfunction "2_2") (pintype "passive"))
    )
    (net (code "60") (name "PB1") (class "Default")
      (node (ref "C7") (pin "2") (pinfunction "2_2") (pintype "passive"))
      (node (ref "IC3") (pin "7") (pinfunction "ADC1/AC1/PB1_7") (pintype "bidirectional"))
      (node (ref "R18") (pin "2") (pinfunction "2_2") (pintype "passive"))
      (node (ref "R24") (pin "1") (pinfunction "1_1") (pintype "passive"))
    )
    (net (code "61") (name "PB2") (class "Default")
      (node (ref "C8") (pin "2") (pinfunction "2_2") (pintype "passive"))
      (node (ref "IC3") (pin "8") (pinfunction "INT/DAC0/ADC2/AC2/PB2_8") (pintype "bidirectional"))
      (node (ref "R19") (pin "2") (pinfunction "2_2") (pintype "passive"))
      (node (ref "R23") (pin "1") (pinfunction "1_1") (pintype "passive"))
    )
    (net (code "62") (name "PB3") (class "Default")
      (node (ref "C11") (pin "2") (pinfunction "2_2") (pintype "passive"))
      (node (ref "IC3") (pin "9") (pinfunction "DAC1/ADC3/AC3/PB3_9") (pintype "bidirectional"))
      (node (ref "R21") (pin "2") (pinfunction "2_2") (pintype "passive"))
      (node (ref "R22") (pin "1") (pinfunction "1_1") (pintype "passive"))
    )
    (net (code "63") (name "VDD") (class "Default")
      (node (ref "C17") (pin "2") (pinfunction "2_2") (pintype "passive"))
      (node (ref "C21") (pin "2") (pinfunction "2_2") (pintype "passive"))
      (node (ref "D1") (pin "C") (pinfunction "C_C") (pintype "passive"))
      (node (ref "D2") (pin "C") (pinfunction "C_C") (pintype "passive"))
      (node (ref "D3") (pin "C") (pinfunction "C_C") (pintype "passive"))
      (node (ref "D4") (pin "C") (pinfunction "C_C") (pintype "passive"))
      (node (ref "D5") (pin "C") (pinfunction "C_C") (pintype "passive"))
      (node (ref "D6") (pin "C") (pinfunction "C_C") (pintype "passive"))
      (node (ref "D7") (pin "C") (pinfunction "C_C") (pintype "passive"))
      (node (ref "D8") (pin "C") (pinfunction "C_C") (pintype "passive"))
      (node (ref "D9") (pin "C") (pinfunction "C_C") (pintype "passive"))
      (node (ref "IC1") (pin "1") (pinfunction "VI_1") (pintype "input"))
    )
    (net (code "64") (name "unconnected-(IC3-CLKO{slash}EVO{slash}TXD1{slash}SCK{slash}PD7-Pad33)") (class "Default")
      (node (ref "IC3") (pin "33") (pinfunction "CLKO/EVO/TXD1/SCK/PD7_33") (pintype "bidirectional"))
    )
    (net (code "65") (name "unconnected-(IC3-CLKO{slash}EVO{slash}TXD1{slash}SCK{slash}TOSC1{slash}PE7-Pad43)") (class "Default")
      (node (ref "IC3") (pin "43") (pinfunction "CLKO/EVO/TXD1/SCK/TOSC1/PE7_43") (pintype "bidirectional"))
    )
    (net (code "66") (name "unconnected-(IC3-EVO{slash}CLKO{slash}TXD1{slash}SCK{slash}OC0DHS{slash}PC7-Pad23)") (class "Default")
      (node (ref "IC3") (pin "23") (pinfunction "EVO/CLKO/TXD1/SCK/OC0DHS/PC7_23") (pintype "bidirectional"))
    )
    (net (code "67") (name "unconnected-(IC3-INT{slash}RXD0{slash}OC0C{slash}PD2-Pad28)") (class "Default")
      (node (ref "IC3") (pin "28") (pinfunction "INT/RXD0/OC0C/PD2_28") (pintype "bidirectional"))
    )
    (net (code "68") (name "unconnected-(IC3-INT{slash}RXD0{slash}OC0C{slash}PF2-Pad48)") (class "Default")
      (node (ref "IC3") (pin "48") (pinfunction "INT/RXD0/OC0C/PF2_48") (pintype "bidirectional"))
    )
    (net (code "69") (name "unconnected-(IC3-OC0A{slash}PF0-Pad46)") (class "Default")
      (node (ref "IC3") (pin "46") (pinfunction "OC0A/PF0_46") (pintype "bidirectional"))
    )
    (net (code "70") (name "unconnected-(IC3-PDI_DATA-Pad56)") (class "Default")
      (node (ref "IC3") (pin "56") (pinfunction "PDI_DATA_56") (pintype "bidirectional"))
    )
    (net (code "71") (name "unconnected-(IC3-PF4-Pad50)") (class "Default")
      (node (ref "IC3") (pin "50") (pinfunction "PF4_50") (pintype "bidirectional"))
    )
    (net (code "72") (name "unconnected-(IC3-PF5-Pad51)") (class "Default")
      (node (ref "IC3") (pin "51") (pinfunction "PF5_51") (pintype "bidirectional"))
    )
    (net (code "73") (name "unconnected-(IC3-PF6-Pad54)") (class "Default")
      (node (ref "IC3") (pin "54") (pinfunction "PF6_54") (pintype "bidirectional"))
    )
    (net (code "74") (name "unconnected-(IC3-PF7-Pad55)") (class "Default")
      (node (ref "IC3") (pin "55") (pinfunction "PF7_55") (pintype "bidirectional"))
    )
    (net (code "75") (name "unconnected-(IC3-PR0(XTAL2)-Pad58)") (class "Default")
      (node (ref "IC3") (pin "58") (pinfunction "PR0(XTAL2)_58") (pintype "passive"))
    )
    (net (code "76") (name "unconnected-(IC3-PR1(XALT1)-Pad59)") (class "Default")
      (node (ref "IC3") (pin "59") (pinfunction "PR1(XALT1)_59") (pintype "passive"))
    )
    (net (code "77") (name "unconnected-(IC3-RXD1{slash}MISO{slash}OC0DLS{slash}PC6-Pad22)") (class "Default")
      (node (ref "IC3") (pin "22") (pinfunction "RXD1/MISO/OC0DLS/PC6_22") (pintype "bidirectional"))
    )
    (net (code "78") (name "unconnected-(IC3-RXD1{slash}MISO{slash}PD6-Pad32)") (class "Default")
      (node (ref "IC3") (pin "32") (pinfunction "RXD1/MISO/PD6_32") (pintype "bidirectional"))
    )
    (net (code "79") (name "unconnected-(IC3-RXD1{slash}MISO{slash}TOSC2{slash}PE6-Pad42)") (class "Default")
      (node (ref "IC3") (pin "42") (pinfunction "RXD1/MISO/TOSC2/PE6_42") (pintype "bidirectional"))
    )
    (net (code "80") (name "unconnected-(IC3-SDA{slash}OC0A{slash}OC0ALS{slash}PC0-Pad16)") (class "Default")
      (node (ref "IC3") (pin "16") (pinfunction "SDA/OC0A/OC0ALS/PC0_16") (pintype "bidirectional"))
    )
    (net (code "81") (name "unconnected-(IC3-SDA{slash}OC0A{slash}PE0-Pad36)") (class "Default")
      (node (ref "IC3") (pin "36") (pinfunction "SDA/OC0A/PE0_36") (pintype "bidirectional"))
    )
    (net (code "82") (name "unconnected-(IC3-TXD0{slash}OC0D{slash}PD3-Pad29)") (class "Default")
      (node (ref "IC3") (pin "29") (pinfunction "TXD0/OC0D/PD3_29") (pintype "bidirectional"))
    )
    (net (code "83") (name "unconnected-(IC3-TXD0{slash}OC0D{slash}PF3-Pad49)") (class "Default")
      (node (ref "IC3") (pin "49") (pinfunction "TXD0/OC0D/PF3_49") (pintype "bidirectional"))
    )
    (net (code "84") (name "unconnected-(IC3-XCK0{slash}OC0B{slash}PF1-Pad47)") (class "Default")
      (node (ref "IC3") (pin "47") (pinfunction "XCK0/OC0B/PF1_47") (pintype "bidirectional"))
    )
    (net (code "85") (name "unconnected-(IC3-XCK1{slash}MOSI{slash}OC0CHS{slash}PC5-Pad21)") (class "Default")
      (node (ref "IC3") (pin "21") (pinfunction "XCK1/MOSI/OC0CHS/PC5_21") (pintype "bidirectional"))
    )
    (net (code "86") (name "unconnected-(IC3-XCK1{slash}MOSI{slash}OC1B{slash}PD5-Pad31)") (class "Default")
      (node (ref "IC3") (pin "31") (pinfunction "XCK1/MOSI/OC1B/PD5_31") (pintype "bidirectional"))
    )
    (net (code "87") (name "unconnected-(IC3-XCK1{slash}MOSI{slash}OC1B{slash}PE5-Pad41)") (class "Default")
      (node (ref "IC3") (pin "41") (pinfunction "XCK1/MOSI/OC1B/PE5_41") (pintype "bidirectional"))
    )
    (net (code "88") (name "unconnected-(IC3-~{RESET}{slash}PDI_CLK-Pad57)") (class "Default")
      (node (ref "IC3") (pin "57") (pinfunction "~{RESET}/PDI_CLK_57") (pintype "input"))
    )
    (net (code "89") (name "unconnected-(IC3-~{SS}{slash}OC1A{slash}PD4-Pad30)") (class "Default")
      (node (ref "IC3") (pin "30") (pinfunction "~{SS}/OC1A/PD4_30") (pintype "bidirectional"))
    )
    (net (code "90") (name "unconnected-(U$1-P2-ACT{slash}DIAG_TX-PadP2)") (class "Default")
      (node (ref "U$1") (pin "P2") (pinfunction "P2-ACT/DIAG_TX_P2") (pintype "bidirectional"))
    )
    (net (code "91") (name "unconnected-(U$1-P3-DCD{slash}DIAG_RX-PadP3)") (class "Default")
      (node (ref "U$1") (pin "P3") (pinfunction "P3-DCD/DIAG_RX_P3") (pintype "bidirectional"))
    )
    (net (code "92") (name "unconnected-(U$1-P4-GPIO0-PadP4)") (class "Default")
      (node (ref "U$1") (pin "P4") (pinfunction "P4-GPIO0_P4") (pintype "bidirectional"))
    )
    (net (code "93") (name "unconnected-(U$1-P7-GPIO4{slash}HOST_CTS-PadP7)") (class "Default")
      (node (ref "U$1") (pin "P7") (pinfunction "P7-GPIO4/HOST_CTS_P7") (pintype "bidirectional"))
    )
    (net (code "94") (name "unconnected-(U$1-P8-GPIO5{slash}HOST_RTS-PadP8)") (class "Default")
      (node (ref "U$1") (pin "P8") (pinfunction "P8-GPIO5/HOST_RTS_P8") (pintype "bidirectional"))
    )
    (net (code "95") (name "unconnected-(U$1-P9-DAC0-PadP9)") (class "Default")
      (node (ref "U$1") (pin "P9") (pinfunction "P9-DAC0_P9") (pintype "bidirectional"))
    )
    (net (code "96") (name "unconnected-(U$1-P10-GPIO2-PadP10)") (class "Default")
      (node (ref "U$1") (pin "P10") (pinfunction "P10-GPIO2_P10") (pintype "bidirectional"))
    )
    (net (code "97") (name "unconnected-(U$1-P11-GPIO1-PadP11)") (class "Default")
      (node (ref "U$1") (pin "P11") (pinfunction "P11-GPIO1_P11") (pintype "bidirectional"))
    )
    (net (code "98") (name "unconnected-(U$1-P12-GPIO3{slash}DAV-PadP12)") (class "Default")
      (node (ref "U$1") (pin "P12") (pinfunction "P12-GPIO3/DAV_P12") (pintype "bidirectional"))
    )
    (net (code "99") (name "unconnected-(U$1-P13-DAC1-PadP13)") (class "Default")
      (node (ref "U$1") (pin "P13") (pinfunction "P13-DAC1_P13") (pintype "bidirectional"))
    )
    (net (code "100") (name "unconnected-(U$1-P17-RESET-PadP17)") (class "Default")
      (node (ref "U$1") (pin "P17") (pinfunction "P17-RESET_P17") (pintype "bidirectional"))
    )
    (net (code "101") (name "unconnected-(U$1-P18-ADC0-PadP18)") (class "Default")
      (node (ref "U$1") (pin "P18") (pinfunction "P18-ADC0_P18") (pintype "bidirectional"))
    )
    (net (code "102") (name "unconnected-(U$1-P19-ADC1-PadP19)") (class "Default")
      (node (ref "U$1") (pin "P19") (pinfunction "P19-ADC1_P19") (pintype "bidirectional"))
    )
    (net (code "103") (name "unconnected-(U$1-P20-MISO-PadP20)") (class "Default")
      (node (ref "U$1") (pin "P20") (pinfunction "P20-MISO_P20") (pintype "bidirectional"))
    )
    (net (code "104") (name "unconnected-(U$1-P21-MOSI-PadP21)") (class "Default")
      (node (ref "U$1") (pin "P21") (pinfunction "P21-MOSI_P21") (pintype "bidirectional"))
    )
    (net (code "105") (name "unconnected-(U$1-P22-SS-PadP22)") (class "Default")
      (node (ref "U$1") (pin "P22") (pinfunction "P22-SS_P22") (pintype "bidirectional"))
    )
    (net (code "106") (name "unconnected-(U$1-P23-SCLK-PadP23)") (class "Default")
      (node (ref "U$1") (pin "P23") (pinfunction "P23-SCLK_P23") (pintype "bidirectional"))
    )
    (net (code "107") (name "unconnected-(U$1-P24-ADC2-PadP24)") (class "Default")
      (node (ref "U$1") (pin "P24") (pinfunction "P24-ADC2_P24") (pintype "bidirectional"))
    )
    (net (code "108") (name "unconnected-(U$1-P25-ADC_EXT_REF-PadP25)") (class "Default")
      (node (ref "U$1") (pin "P25") (pinfunction "P25-ADC_EXT_REF_P25") (pintype "bidirectional"))
    )
    (net (code "109") (name "unconnected-(U$1-P26-RSVD-PadP26)") (class "Default")
      (node (ref "U$1") (pin "P26") (pinfunction "P26-RSVD_P26") (pintype "bidirectional"))
    )
    (net (code "110") (name "unconnected-(U$1-P27-RSVD-PadP27)") (class "Default")
      (node (ref "U$1") (pin "P27") (pinfunction "P27-RSVD_P27") (pintype "bidirectional"))
    )
    (net (code "111") (name "unconnected-(U$1-P28-GND-PadP28)") (class "Default")
      (node (ref "U$1") (pin "P28") (pinfunction "P28-GND_P28") (pintype "bidirectional"))
    )
    (net (code "112") (name "unconnected-(U$1-P29-RSVD-PadP29)") (class "Default")
      (node (ref "U$1") (pin "P29") (pinfunction "P29-RSVD_P29") (pintype "bidirectional"))
    )
    (net (code "113") (name "unconnected-(U$2-CBS2-PadP$5)") (class "Default")
      (node (ref "U$2") (pin "P$5") (pinfunction "CBS2_P$5") (pintype "bidirectional"))
    )
    (net (code "114") (name "unconnected-(U$2-CSB-PadP$4)") (class "Default")
      (node (ref "U$2") (pin "P$4") (pinfunction "CSB_P$4") (pintype "bidirectional"))
    )
    (net (code "115") (name "unconnected-(U$2-SDO-PadP$6)") (class "Default")
      (node (ref "U$2") (pin "P$6") (pinfunction "SDO_P$6") (pintype "bidirectional"))
    )
    (net (code "116") (name "unconnected-(U$3-P2-NC-PadP2)") (class "Default")
      (node (ref "U$3") (pin "P2") (pinfunction "P2-NC_P2") (pintype "bidirectional"))
    )
    (net (code "117") (name "unconnected-(U$3-P3-NC-PadP3)") (class "Default")
      (node (ref "U$3") (pin "P3") (pinfunction "P3-NC_P3") (pintype "bidirectional"))
    )
    (net (code "118") (name "unconnected-(U$3-P4-NC-PadP4)") (class "Default")
      (node (ref "U$3") (pin "P4") (pinfunction "P4-NC_P4") (pintype "bidirectional"))
    )
    (net (code "119") (name "unconnected-(U$3-P5-NC-PadP5)") (class "Default")
      (node (ref "U$3") (pin "P5") (pinfunction "P5-NC_P5") (pintype "bidirectional"))
    )
    (net (code "120") (name "unconnected-(U$3-P6-AUX_DA-PadP6)") (class "Default")
      (node (ref "U$3") (pin "P6") (pinfunction "P6-AUX_DA_P6") (pintype "bidirectional"))
    )
    (net (code "121") (name "unconnected-(U$3-P7-AUX_CL-PadP7)") (class "Default")
      (node (ref "U$3") (pin "P7") (pinfunction "P7-AUX_CL_P7") (pintype "bidirectional"))
    )
    (net (code "122") (name "unconnected-(U$3-P12-INT-PadP12)") (class "Default")
      (node (ref "U$3") (pin "P12") (pinfunction "P12-INT_P12") (pintype "bidirectional"))
    )
    (net (code "123") (name "unconnected-(U$3-P14-NC-PadP14)") (class "Default")
      (node (ref "U$3") (pin "P14") (pinfunction "P14-NC_P14") (pintype "bidirectional"))
    )
    (net (code "124") (name "unconnected-(U$3-P15-NC-PadP15)") (class "Default")
      (node (ref "U$3") (pin "P15") (pinfunction "P15-NC_P15") (pintype "bidirectional"))
    )
    (net (code "125") (name "unconnected-(U$3-P16-NC-PadP16)") (class "Default")
      (node (ref "U$3") (pin "P16") (pinfunction "P16-NC_P16") (pintype "bidirectional"))
    )
    (net (code "126") (name "unconnected-(U$3-P17-NC-PadP17)") (class "Default")
      (node (ref "U$3") (pin "P17") (pinfunction "P17-NC_P17") (pintype "bidirectional"))
    )
    (net (code "127") (name "unconnected-(U$3-P19-RESV-PadP19)") (class "Default")
      (node (ref "U$3") (pin "P19") (pinfunction "P19-RESV_P19") (pintype "bidirectional"))
    )
    (net (code "128") (name "unconnected-(U$3-P21-RESV-PadP21)") (class "Default")
      (node (ref "U$3") (pin "P21") (pinfunction "P21-RESV_P21") (pintype "bidirectional"))
    )
    (net (code "129") (name "unconnected-(U$3-P22-CLKOUT-PadP22)") (class "Default")
      (node (ref "U$3") (pin "P22") (pinfunction "P22-CLKOUT_P22") (pintype "bidirectional"))
    )
  )
)
